# payload_detect.net
KiCad netlist of a schematic drawn in Altium Designer
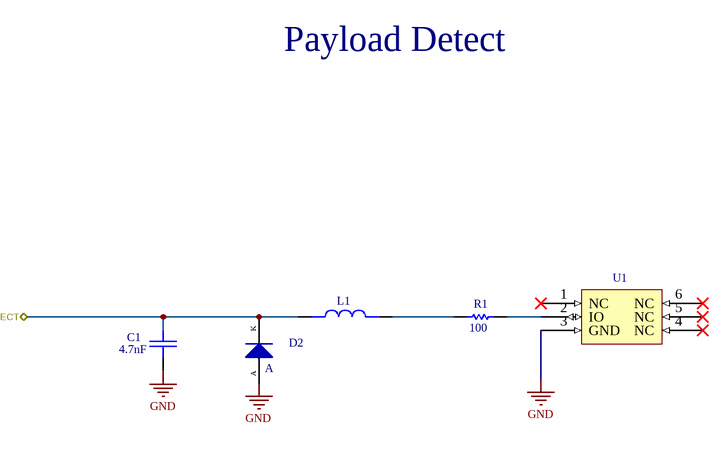
[diagram p0: payload_detect.SchDoc]

(export (version "E")
  (design (tool "Eeschema 10.0.6"))
  (components
    (comp (ref "C1")
      (value "4.7nF")
      (footprint "CAP-0402-A")
      (description "CAP 0402 4700PF 50V 10% X7R")
      (libsource (lib "Picatinny Server") (part "Capacitor - Non-Polarized"))
    )
    (comp (ref "D2")
      (value "A")
      (footprint "DI-SOD123F-A")
      (description "TVS Diodes & ESD Suppressors; P4FL3.3A_R1_00001; PANJIT; 3.3 V; 5.2 V")
      (libsource (lib "Picatinny Server") (part "Diode"))
    )
    (comp (ref "L1")
      (value "MDF2016BSS270C")
      (footprint "IND-0806-A")
      (description "Ferrite Bead, Aec-Q200, 0806, 1A Rohs Compliant: Yes")
      (libsource (lib "Picatinny Server") (part "Inductor"))
    )
    (comp (ref "R1")
      (value "100")
      (footprint "RES-0402-B")
      (description "Res 0402 100 Ohm 0.1W 1% Thick Film")
      (libsource (lib "Picatinny Server") (part "Resistor"))
    )
    (comp (ref "U1")
      (value "DS2431Q-TR")
      (footprint "IC-TDFN3X3-B")
      (description "IC EEPROM 1KBIT 1-WIRE 6TDFN")
      (libsource (lib "Picatinny Server") (part "DS2431Q-TR"))
    )
  )
  (nets
    (net (code "1") (name "/DETECT") (class "Default")
      (node (ref "C1") (pin "2") (pinfunction "2_2") (pintype "passive"))
      (node (ref "D2") (pin "K") (pinfunction "K_K") (pintype "passive"))
      (node (ref "L1") (pin "1") (pinfunction "1_1") (pintype "passive"))
    )
    (net (code "2") (name "GND") (class "Default")
      (node (ref "C1") (pin "1") (pinfunction "1_1") (pintype "passive"))
      (node (ref "U1") (pin "3") (pinfunction "GND_3") (pintype "input"))
    )
    (net (code "3") (name "Net-(L1-Pad2)") (class "Default")
      (node (ref "L1") (pin "2") (pinfunction "2_2") (pintype "passive"))
      (node (ref "R1") (pin "1") (pinfunction "1_1") (pintype "passive"))
    )
    (net (code "4") (name "Net-(U1-IO)") (class "Default")
      (node (ref "R1") (pin "2") (pinfunction "2_2") (pintype "passive"))
      (node (ref "U1") (pin "2") (pinfunction "IO_2") (pintype "bidirectional"))
    )
    (net (code "5") (name "unconnected-(D2-PadA)") (class "Default")
      (node (ref "D2") (pin "A") (pinfunction "A_A") (pintype "passive"))
    )
    (net (code "6") (name "unconnected-(U1-NC-Pad1)") (class "Default")
      (node (ref "U1") (pin "1") (pinfunction "NC_1") (pintype "input+no_connect"))
    )
    (net (code "7") (name "unconnected-(U1-NC-Pad4)") (class "Default")
      (node (ref "U1") (pin "4") (pinfunction "NC_4") (pintype "input+no_connect"))
    )
    (net (code "8") (name "unconnected-(U1-NC-Pad5)") (class "Default")
      (node (ref "U1") (pin "5") (pinfunction "NC_5") (pintype "input+no_connect"))
    )
    (net (code "9") (name "unconnected-(U1-NC-Pad6)") (class "Default")
      (node (ref "U1") (pin "6") (pinfunction "NC_6") (pintype "input+no_connect"))
    )
  )
)
